# motor_driver_breakout.net
KiCad netlist of a schematic drawn in EAGLE
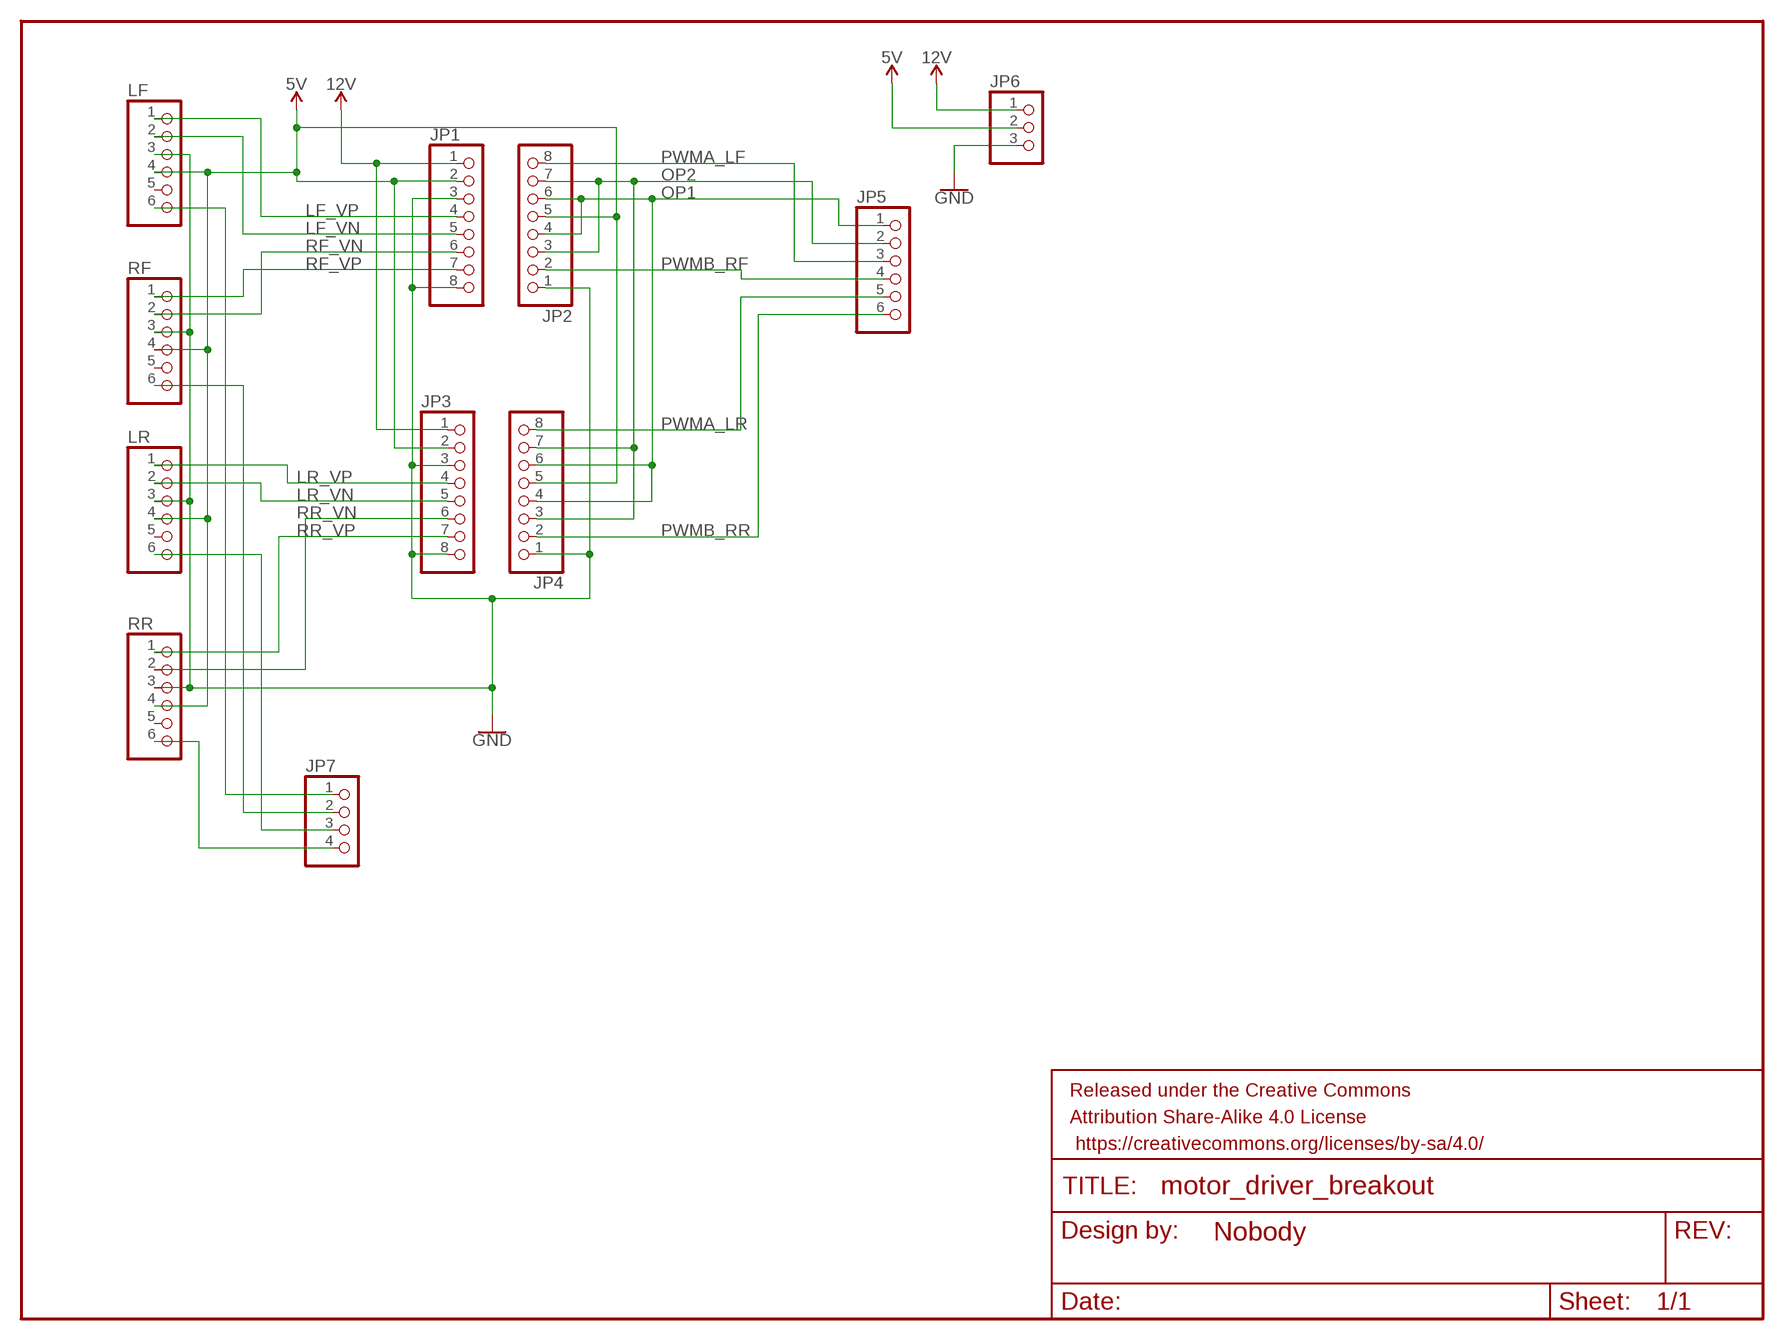
[diagram p0: schematic, sheet 1]

(export (version "E")
  (design (tool "Eeschema 10.0.6"))
  (components
    (comp (ref "FRAME1")
      (value "FRAME-LETTERNO_PACKAGE")
      (footprint "eagle-import:DUMMY")
      (fields (field (name "DESIGNER") "Nobody"))
      (libsource (lib "eagle-import") (part "FRAME-LETTERNO_PACKAGE"))
    )
    (comp (ref "JP1")
      (value "PINHD-1X8")
      (footprint "eagle-import:1X08")
      (libsource (lib "eagle-import") (part "PINHD-1X8"))
    )
    (comp (ref "JP2")
      (value "PINHD-1X8")
      (footprint "eagle-import:1X08")
      (libsource (lib "eagle-import") (part "PINHD-1X8"))
    )
    (comp (ref "JP3")
      (value "PINHD-1X8")
      (footprint "eagle-import:1X08")
      (libsource (lib "eagle-import") (part "PINHD-1X8"))
    )
    (comp (ref "JP4")
      (value "PINHD-1X8")
      (footprint "eagle-import:1X08")
      (libsource (lib "eagle-import") (part "PINHD-1X8"))
    )
    (comp (ref "JP5")
      (value "PINHD-1X6")
      (footprint "eagle-import:1X06")
      (libsource (lib "eagle-import") (part "PINHD-1X6"))
    )
    (comp (ref "JP6")
      (value "PINHD-1X3")
      (footprint "eagle-import:1X03")
      (libsource (lib "eagle-import") (part "PINHD-1X3"))
    )
    (comp (ref "JP7")
      (value "PINHD-1X4")
      (footprint "eagle-import:1X04")
      (libsource (lib "eagle-import") (part "PINHD-1X4"))
    )
    (comp (ref "LF")
      (value "PINHD-1X6")
      (footprint "eagle-import:1X06")
      (libsource (lib "eagle-import") (part "PINHD-1X6"))
    )
    (comp (ref "LR")
      (value "PINHD-1X6")
      (footprint "eagle-import:1X06")
      (libsource (lib "eagle-import") (part "PINHD-1X6"))
    )
    (comp (ref "RF")
      (value "PINHD-1X6")
      (footprint "eagle-import:1X06")
      (libsource (lib "eagle-import") (part "PINHD-1X6"))
    )
    (comp (ref "RR")
      (value "PINHD-1X6")
      (footprint "eagle-import:1X06")
      (libsource (lib "eagle-import") (part "PINHD-1X6"))
    )
  )
  (nets
    (net (code "1") (name "/LF_VN") (class "Default")
      (node (ref "JP1") (pin "5") (pinfunction "5_5") (pintype "passive"))
      (node (ref "LF") (pin "2") (pinfunction "2_2") (pintype "passive"))
    )
    (net (code "2") (name "/LF_VP") (class "Default")
      (node (ref "JP1") (pin "4") (pinfunction "4_4") (pintype "passive"))
      (node (ref "LF") (pin "1") (pinfunction "1_1") (pintype "passive"))
    )
    (net (code "3") (name "/LR_VN") (class "Default")
      (node (ref "JP3") (pin "5") (pinfunction "5_5") (pintype "passive"))
      (node (ref "LR") (pin "2") (pinfunction "2_2") (pintype "passive"))
    )
    (net (code "4") (name "/LR_VP") (class "Default")
      (node (ref "JP3") (pin "4") (pinfunction "4_4") (pintype "passive"))
      (node (ref "LR") (pin "1") (pinfunction "1_1") (pintype "passive"))
    )
    (net (code "5") (name "/OP1") (class "Default")
      (node (ref "JP2") (pin "4") (pinfunction "4_4") (pintype "passive"))
      (node (ref "JP2") (pin "6") (pinfunction "6_6") (pintype "passive"))
      (node (ref "JP4") (pin "4") (pinfunction "4_4") (pintype "passive"))
      (node (ref "JP4") (pin "6") (pinfunction "6_6") (pintype "passive"))
      (node (ref "JP5") (pin "1") (pinfunction "1_1") (pintype "passive"))
    )
    (net (code "6") (name "/OP2") (class "Default")
      (node (ref "JP2") (pin "3") (pinfunction "3_3") (pintype "passive"))
      (node (ref "JP2") (pin "7") (pinfunction "7_7") (pintype "passive"))
      (node (ref "JP4") (pin "3") (pinfunction "3_3") (pintype "passive"))
      (node (ref "JP4") (pin "7") (pinfunction "7_7") (pintype "passive"))
      (node (ref "JP5") (pin "2") (pinfunction "2_2") (pintype "passive"))
    )
    (net (code "7") (name "/PWMA_LF") (class "Default")
      (node (ref "JP2") (pin "8") (pinfunction "8_8") (pintype "passive"))
      (node (ref "JP5") (pin "3") (pinfunction "3_3") (pintype "passive"))
    )
    (net (code "8") (name "/PWMA_LR") (class "Default")
      (node (ref "JP4") (pin "8") (pinfunction "8_8") (pintype "passive"))
      (node (ref "JP5") (pin "5") (pinfunction "5_5") (pintype "passive"))
    )
    (net (code "9") (name "/PWMB_RF") (class "Default")
      (node (ref "JP2") (pin "2") (pinfunction "2_2") (pintype "passive"))
      (node (ref "JP5") (pin "4") (pinfunction "4_4") (pintype "passive"))
    )
    (net (code "10") (name "/PWMB_RR") (class "Default")
      (node (ref "JP4") (pin "2") (pinfunction "2_2") (pintype "passive"))
      (node (ref "JP5") (pin "6") (pinfunction "6_6") (pintype "passive"))
    )
    (net (code "11") (name "/RF_VN") (class "Default")
      (node (ref "JP1") (pin "6") (pinfunction "6_6") (pintype "passive"))
      (node (ref "RF") (pin "2") (pinfunction "2_2") (pintype "passive"))
    )
    (net (code "12") (name "/RF_VP") (class "Default")
      (node (ref "JP1") (pin "7") (pinfunction "7_7") (pintype "passive"))
      (node (ref "RF") (pin "1") (pinfunction "1_1") (pintype "passive"))
    )
    (net (code "13") (name "/RR_VN") (class "Default")
      (node (ref "JP3") (pin "6") (pinfunction "6_6") (pintype "passive"))
      (node (ref "RR") (pin "2") (pinfunction "2_2") (pintype "passive"))
    )
    (net (code "14") (name "/RR_VP") (class "Default")
      (node (ref "JP3") (pin "7") (pinfunction "7_7") (pintype "passive"))
      (node (ref "RR") (pin "1") (pinfunction "1_1") (pintype "passive"))
    )
    (net (code "15") (name "5V") (class "Default")
      (node (ref "JP1") (pin "2") (pinfunction "2_2") (pintype "passive"))
      (node (ref "JP2") (pin "5") (pinfunction "5_5") (pintype "passive"))
      (node (ref "JP3") (pin "2") (pinfunction "2_2") (pintype "passive"))
      (node (ref "JP4") (pin "5") (pinfunction "5_5") (pintype "passive"))
      (node (ref "JP6") (pin "2") (pinfunction "2_2") (pintype "passive"))
      (node (ref "LF") (pin "4") (pinfunction "4_4") (pintype "passive"))
      (node (ref "LR") (pin "4") (pinfunction "4_4") (pintype "passive"))
      (node (ref "RF") (pin "4") (pinfunction "4_4") (pintype "passive"))
      (node (ref "RR") (pin "4") (pinfunction "4_4") (pintype "passive"))
    )
    (net (code "16") (name "12V") (class "Default")
      (node (ref "JP1") (pin "1") (pinfunction "1_1") (pintype "passive"))
      (node (ref "JP3") (pin "1") (pinfunction "1_1") (pintype "passive"))
      (node (ref "JP6") (pin "1") (pinfunction "1_1") (pintype "passive"))
    )
    (net (code "17") (name "GND") (class "Default")
      (node (ref "JP1") (pin "3") (pinfunction "3_3") (pintype "passive"))
      (node (ref "JP1") (pin "8") (pinfunction "8_8") (pintype "passive"))
      (node (ref "JP2") (pin "1") (pinfunction "1_1") (pintype "passive"))
      (node (ref "JP3") (pin "3") (pinfunction "3_3") (pintype "passive"))
      (node (ref "JP3") (pin "8") (pinfunction "8_8") (pintype "passive"))
      (node (ref "JP4") (pin "1") (pinfunction "1_1") (pintype "passive"))
      (node (ref "JP6") (pin "3") (pinfunction "3_3") (pintype "passive"))
      (node (ref "LF") (pin "3") (pinfunction "3_3") (pintype "passive"))
      (node (ref "LR") (pin "3") (pinfunction "3_3") (pintype "passive"))
      (node (ref "RF") (pin "3") (pinfunction "3_3") (pintype "passive"))
      (node (ref "RR") (pin "3") (pinfunction "3_3") (pintype "passive"))
    )
    (net (code "18") (name "Net-(JP7-Pad1)") (class "Default")
      (node (ref "JP7") (pin "1") (pinfunction "1_1") (pintype "passive"))
      (node (ref "LF") (pin "6") (pinfunction "6_6") (pintype "passive"))
    )
    (net (code "19") (name "Net-(JP7-Pad2)") (class "Default")
      (node (ref "JP7") (pin "2") (pinfunction "2_2") (pintype "passive"))
      (node (ref "RF") (pin "6") (pinfunction "6_6") (pintype "passive"))
    )
    (net (code "20") (name "Net-(JP7-Pad3)") (class "Default")
      (node (ref "JP7") (pin "3") (pinfunction "3_3") (pintype "passive"))
      (node (ref "LR") (pin "6") (pinfunction "6_6") (pintype "passive"))
    )
    (net (code "21") (name "Net-(JP7-Pad4)") (class "Default")
      (node (ref "JP7") (pin "4") (pinfunction "4_4") (pintype "passive"))
      (node (ref "RR") (pin "6") (pinfunction "6_6") (pintype "passive"))
    )
    (net (code "22") (name "unconnected-(LF-Pad5)") (class "Default")
      (node (ref "LF") (pin "5") (pinfunction "5_5") (pintype "passive"))
    )
    (net (code "23") (name "unconnected-(LR-Pad5)") (class "Default")
      (node (ref "LR") (pin "5") (pinfunction "5_5") (pintype "passive"))
    )
    (net (code "24") (name "unconnected-(RF-Pad5)") (class "Default")
      (node (ref "RF") (pin "5") (pinfunction "5_5") (pintype "passive"))
    )
    (net (code "25") (name "unconnected-(RR-Pad5)") (class "Default")
      (node (ref "RR") (pin "5") (pinfunction "5_5") (pintype "passive"))
    )
  )
)
